# SCH_Esp12_Power_Module_2022-09-06.net
KiCad netlist of a schematic drawn in EasyEDA
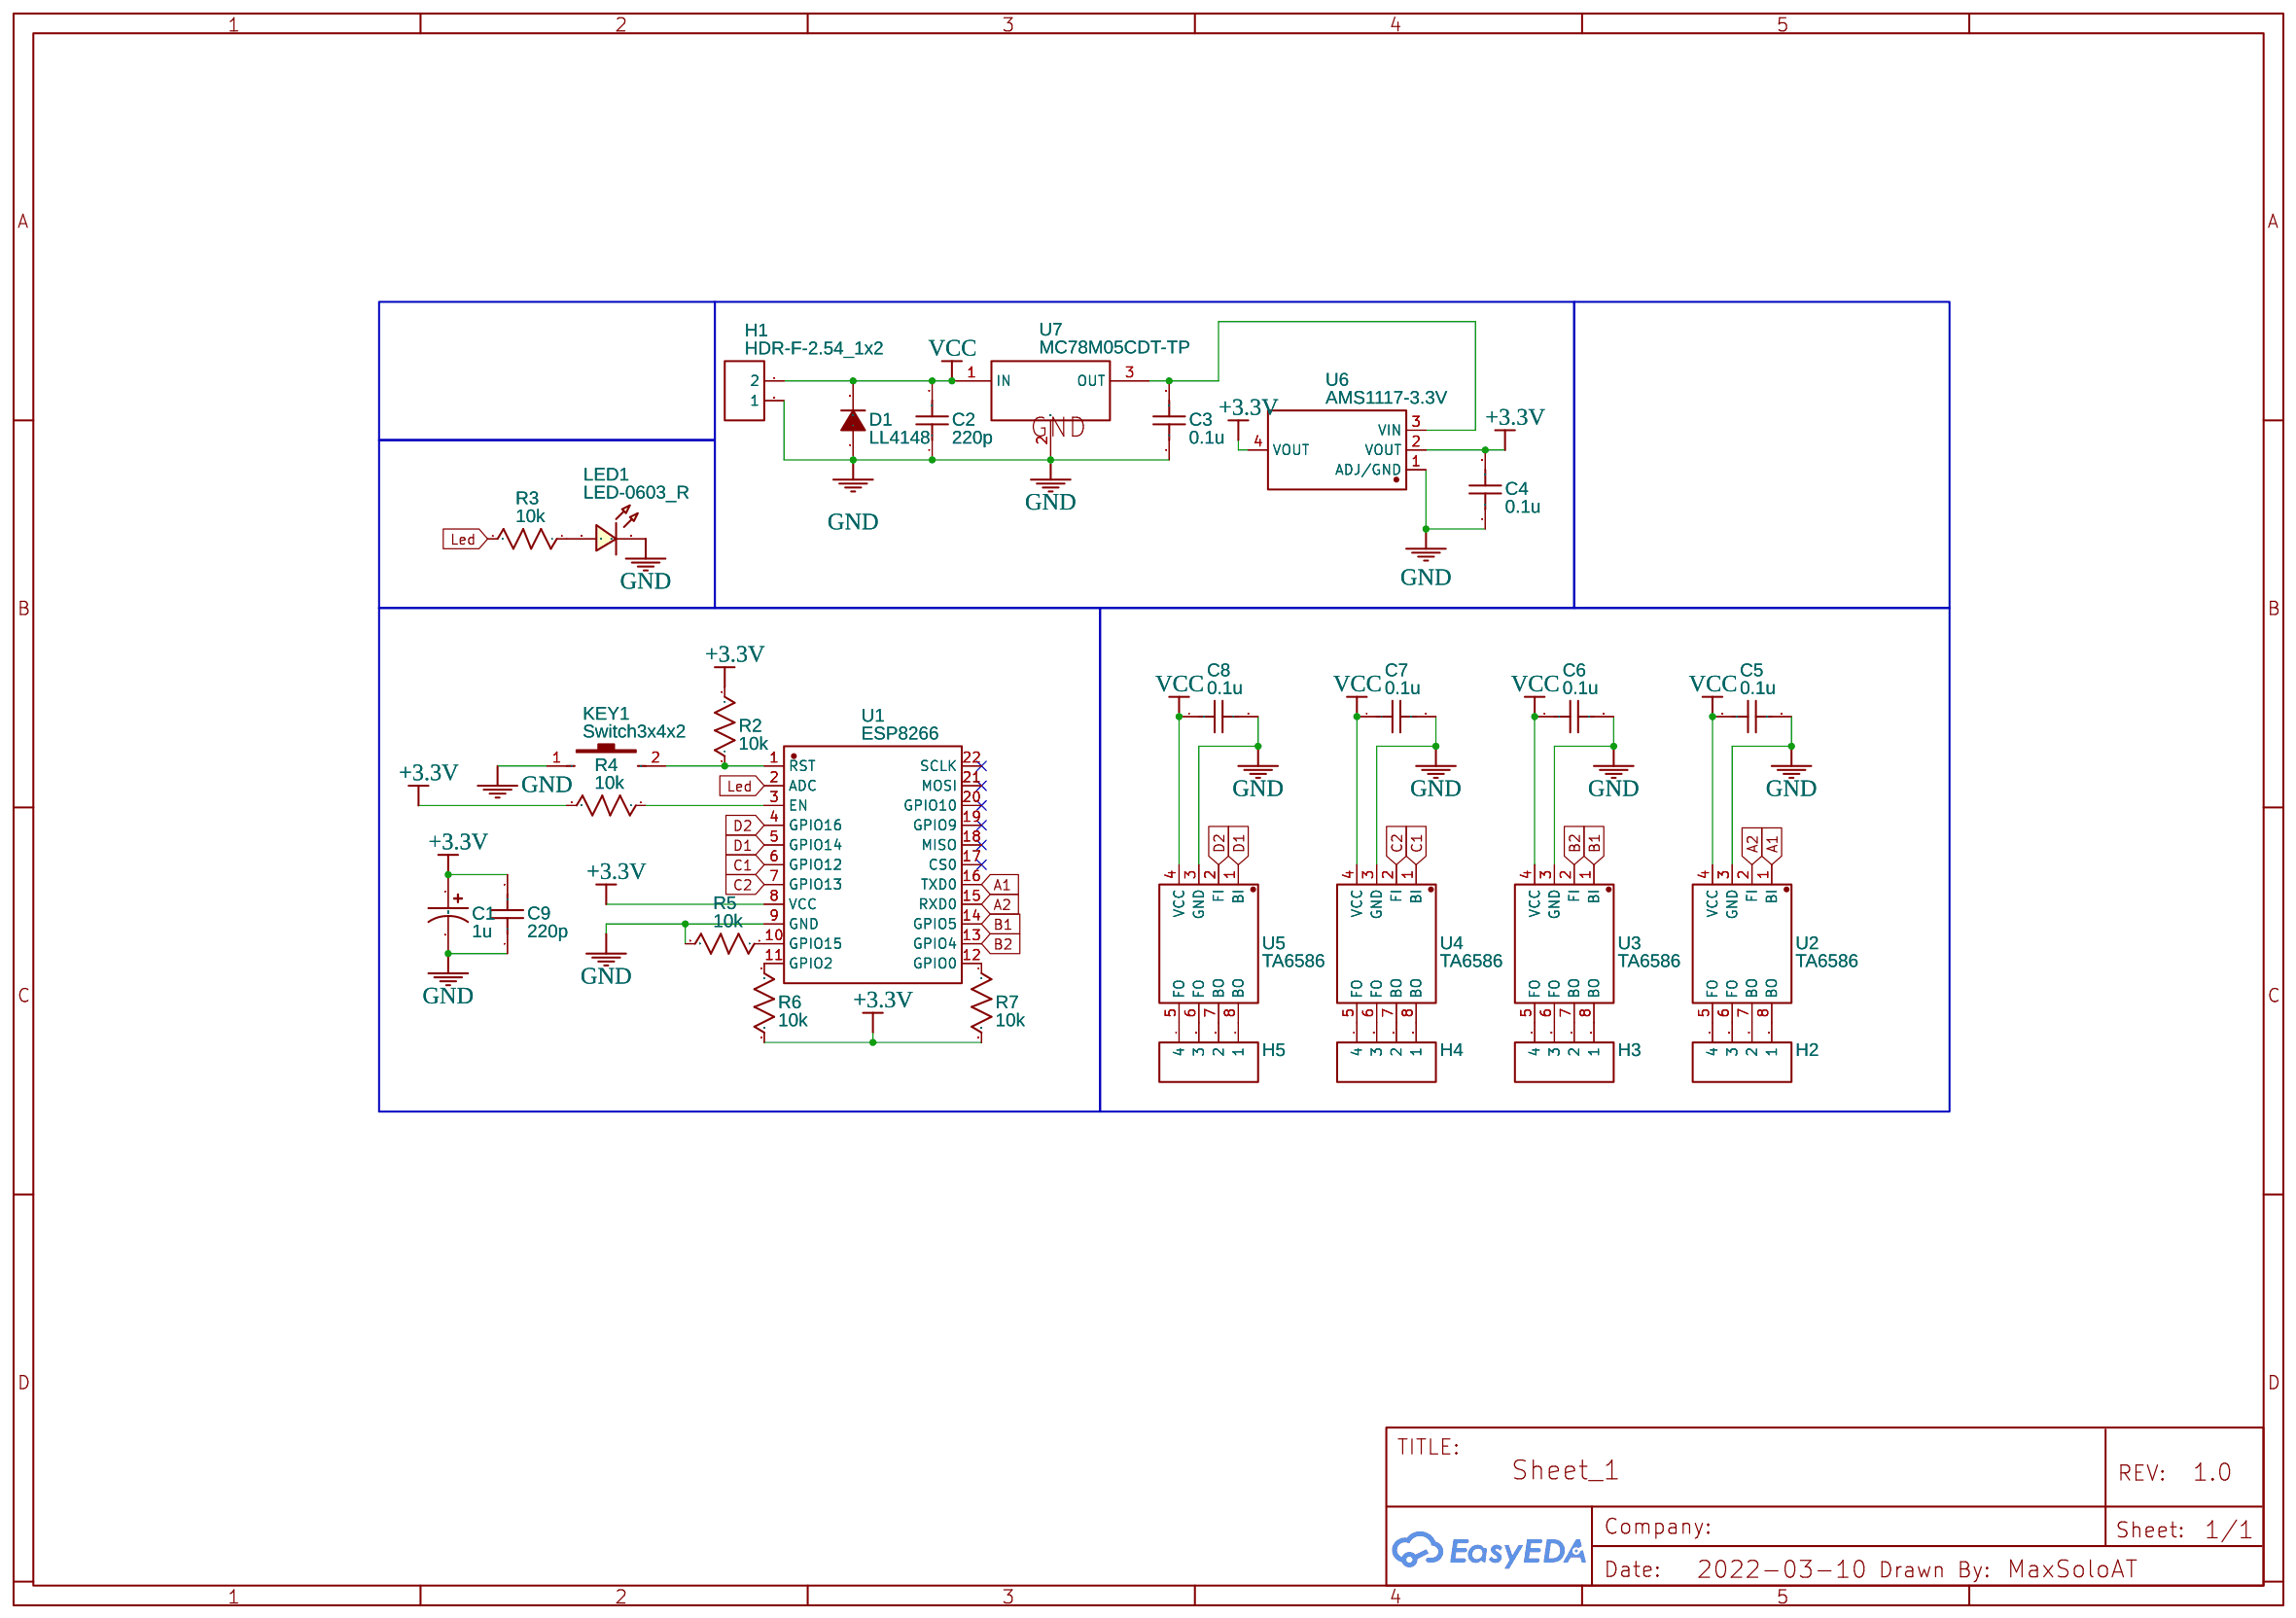
[diagram p0: schematic sheet]

(export (version "E")
  (design (tool "Eeschema 10.0.6"))
  (components
    (comp (ref "C1") (value "1u") (libsource (lib "") (part "C_Tan_SMD_B_US")))
    (comp (ref "C2") (value "220p") (libsource (lib "") (part "C_0603_US")))
    (comp (ref "C3") (value "0.1u") (libsource (lib "") (part "C_0603_US")))
    (comp (ref "C4") (value "0.1u") (libsource (lib "") (part "C_0603_US")))
    (comp (ref "C5") (value "0.1u") (libsource (lib "") (part "C_0603_US_1")))
    (comp (ref "C6") (value "0.1u") (libsource (lib "") (part "C_0603_US_1")))
    (comp (ref "C7") (value "0.1u") (libsource (lib "") (part "C_0603_US_1")))
    (comp (ref "C8") (value "0.1u") (libsource (lib "") (part "C_0603_US_1")))
    (comp (ref "C9") (value "220p") (libsource (lib "") (part "C_0603_US")))
    (comp (ref "D1")
      (value "LL4148")
      (fields (field (name "BOM_Supplier Part") "C9808"))
      (libsource (lib "") (part "LL4148"))
    )
    (comp (ref "H1")
      (value "HDR-F-2.54_1x2")
      (fields (field (name "BOM_Supplier Part") "C49661"))
      (libsource (lib "") (part "HDR-F-2.54_1x2"))
    )
    (comp (ref "H2")
      (value "HDR-F-2.54_1x4")
      (fields (field (name "BOM_Supplier Part") "C225501"))
      (libsource (lib "") (part "HDR-F-2.54_1x4"))
    )
    (comp (ref "H3")
      (value "HDR-F-2.54_1x4")
      (fields (field (name "BOM_Supplier Part") "C225501"))
      (libsource (lib "") (part "HDR-F-2.54_1x4"))
    )
    (comp (ref "H4")
      (value "HDR-F-2.54_1x4")
      (fields (field (name "BOM_Supplier Part") "C225501"))
      (libsource (lib "") (part "HDR-F-2.54_1x4"))
    )
    (comp (ref "H5")
      (value "HDR-F-2.54_1x4")
      (fields (field (name "BOM_Supplier Part") "C225501"))
      (libsource (lib "") (part "HDR-F-2.54_1x4"))
    )
    (comp (ref "KEY1")
      (value "Switch3x4x2")
      (fields (field (name "BOM_Supplier Part") "C26638"))
      (libsource (lib "") (part "Switch3x4x2"))
    )
    (comp (ref "LED1")
      (value "LED-0603_R")
      (fields
        (field (name "BOM_Manufacturer Part") "19-217/R6C-AL1M2VY/3T")
        (field (name "BOM_Supplier Part") "C72044")
      )
      (libsource (lib "") (part "LED-0603_R"))
    )
    (comp (ref "R2") (value "10k") (libsource (lib "") (part "R_0603_US_2")))
    (comp (ref "R3") (value "10k") (libsource (lib "") (part "R_0603_US_1")))
    (comp (ref "R4") (value "10k") (libsource (lib "") (part "R_0603_US_1")))
    (comp (ref "R5") (value "10k") (libsource (lib "") (part "R_0603_US_1")))
    (comp (ref "R6") (value "10k") (libsource (lib "") (part "R_0603_US")))
    (comp (ref "R7") (value "10k") (libsource (lib "") (part "R_0603_US")))
    (comp (ref "U1")
      (value "ESP8266")
      (fields (field (name "BOM_Supplier Part") "C9900003049"))
      (libsource (lib "") (part "ESP8266"))
    )
    (comp (ref "U2")
      (value "TA6586")
      (fields (field (name "BOM_Supplier Part") "C128851"))
      (libsource (lib "") (part "TA6586"))
    )
    (comp (ref "U3")
      (value "TA6586")
      (fields (field (name "BOM_Supplier Part") "C128851"))
      (libsource (lib "") (part "TA6586"))
    )
    (comp (ref "U4")
      (value "TA6586")
      (fields (field (name "BOM_Supplier Part") "C128851"))
      (libsource (lib "") (part "TA6586"))
    )
    (comp (ref "U5")
      (value "TA6586")
      (fields (field (name "BOM_Supplier Part") "C128851"))
      (libsource (lib "") (part "TA6586"))
    )
    (comp (ref "U6")
      (value "AMS1117-3.3V")
      (fields (field (name "BOM_Supplier Part") "C2688239"))
      (libsource (lib "") (part "AMS1117-3.3V"))
    )
    (comp (ref "U7")
      (value "MC78M05CDT-TP")
      (fields (field (name "BOM_Supplier Part") "C194250"))
      (libsource (lib "") (part "MC78M05CDT-TP"))
    )
  )
  (nets
    (net (code "1") (name "+3.3V") (class "Default")
      (node (ref "C1") (pin "1") (pinfunction "1_1") (pintype "unspecified"))
      (node (ref "C4") (pin "2") (pinfunction "2_2") (pintype "unspecified"))
      (node (ref "C9") (pin "2") (pinfunction "2_2") (pintype "unspecified"))
      (node (ref "R2") (pin "2") (pinfunction "2_2") (pintype "unspecified"))
      (node (ref "R4") (pin "2") (pinfunction "2_2") (pintype "unspecified"))
      (node (ref "R6") (pin "2") (pinfunction "2_2") (pintype "unspecified"))
      (node (ref "R7") (pin "2") (pinfunction "2_2") (pintype "unspecified"))
      (node (ref "U1") (pin "8") (pinfunction "VCC_8") (pintype "unspecified"))
      (node (ref "U6") (pin "2") (pinfunction "VOUT_2") (pintype "unspecified"))
      (node (ref "U6") (pin "4") (pinfunction "VOUT_4") (pintype "unspecified"))
    )
    (net (code "2") (name "A1") (class "Default")
      (node (ref "U1") (pin "16") (pinfunction "TXD0_16") (pintype "unspecified"))
      (node (ref "U2") (pin "1") (pinfunction "BI_1") (pintype "unspecified"))
    )
    (net (code "3") (name "A2") (class "Default")
      (node (ref "U1") (pin "15") (pinfunction "RXD0_15") (pintype "unspecified"))
      (node (ref "U2") (pin "2") (pinfunction "FI_2") (pintype "unspecified"))
    )
    (net (code "4") (name "B1") (class "Default")
      (node (ref "U1") (pin "14") (pinfunction "GPIO5_14") (pintype "unspecified"))
      (node (ref "U3") (pin "1") (pinfunction "BI_1") (pintype "unspecified"))
    )
    (net (code "5") (name "B2") (class "Default")
      (node (ref "U1") (pin "13") (pinfunction "GPIO4_13") (pintype "unspecified"))
      (node (ref "U3") (pin "2") (pinfunction "FI_2") (pintype "unspecified"))
    )
    (net (code "6") (name "C1") (class "Default")
      (node (ref "U1") (pin "6") (pinfunction "GPIO12_6") (pintype "unspecified"))
      (node (ref "U4") (pin "1") (pinfunction "BI_1") (pintype "unspecified"))
    )
    (net (code "7") (name "C2") (class "Default")
      (node (ref "U1") (pin "7") (pinfunction "GPIO13_7") (pintype "unspecified"))
      (node (ref "U4") (pin "2") (pinfunction "FI_2") (pintype "unspecified"))
    )
    (net (code "8") (name "D1") (class "Default")
      (node (ref "U1") (pin "5") (pinfunction "GPIO14_5") (pintype "unspecified"))
      (node (ref "U5") (pin "1") (pinfunction "BI_1") (pintype "unspecified"))
    )
    (net (code "9") (name "D2") (class "Default")
      (node (ref "U1") (pin "4") (pinfunction "GPIO16_4") (pintype "unspecified"))
      (node (ref "U5") (pin "2") (pinfunction "FI_2") (pintype "unspecified"))
    )
    (net (code "10") (name "GND") (class "Default")
      (node (ref "C1") (pin "2") (pinfunction "2_2") (pintype "unspecified"))
      (node (ref "C2") (pin "1") (pinfunction "1_1") (pintype "unspecified"))
      (node (ref "C3") (pin "1") (pinfunction "1_1") (pintype "unspecified"))
      (node (ref "C4") (pin "1") (pinfunction "1_1") (pintype "unspecified"))
      (node (ref "C5") (pin "2") (pinfunction "2_2") (pintype "unspecified"))
      (node (ref "C6") (pin "2") (pinfunction "2_2") (pintype "unspecified"))
      (node (ref "C7") (pin "2") (pinfunction "2_2") (pintype "unspecified"))
      (node (ref "C8") (pin "2") (pinfunction "2_2") (pintype "unspecified"))
      (node (ref "C9") (pin "1") (pinfunction "1_1") (pintype "unspecified"))
      (node (ref "D1") (pin "1") (pinfunction "A_1") (pintype "unspecified"))
      (node (ref "H1") (pin "1") (pinfunction "1_1") (pintype "input"))
      (node (ref "KEY1") (pin "1") (pinfunction "1_1") (pintype "input"))
      (node (ref "LED1") (pin "2") (pinfunction "2_2") (pintype "unspecified"))
      (node (ref "R5") (pin "2") (pinfunction "2_2") (pintype "unspecified"))
      (node (ref "U1") (pin "9") (pinfunction "GND_9") (pintype "unspecified"))
      (node (ref "U2") (pin "3") (pinfunction "GND_3") (pintype "unspecified"))
      (node (ref "U3") (pin "3") (pinfunction "GND_3") (pintype "unspecified"))
      (node (ref "U4") (pin "3") (pinfunction "GND_3") (pintype "unspecified"))
      (node (ref "U5") (pin "3") (pinfunction "GND_3") (pintype "unspecified"))
      (node (ref "U6") (pin "1") (pinfunction "ADJ/GND_1") (pintype "unspecified"))
      (node (ref "U7") (pin "2") (pinfunction "GND_2") (pintype "passive"))
    )
    (net (code "11") (name "Led") (class "Default")
      (node (ref "R3") (pin "2") (pinfunction "2_2") (pintype "unspecified"))
      (node (ref "U1") (pin "2") (pinfunction "ADC_2") (pintype "unspecified"))
    )
    (net (code "12") (name "Net-(H2-Pad1)") (class "Default")
      (node (ref "H2") (pin "1") (pinfunction "1_1") (pintype "unspecified"))
      (node (ref "U2") (pin "8") (pinfunction "BO_8") (pintype "unspecified"))
    )
    (net (code "13") (name "Net-(H2-Pad2)") (class "Default")
      (node (ref "H2") (pin "2") (pinfunction "2_2") (pintype "unspecified"))
      (node (ref "U2") (pin "7") (pinfunction "BO_7") (pintype "unspecified"))
    )
    (net (code "14") (name "Net-(H2-Pad3)") (class "Default")
      (node (ref "H2") (pin "3") (pinfunction "3_3") (pintype "unspecified"))
      (node (ref "U2") (pin "6") (pinfunction "FO_6") (pintype "unspecified"))
    )
    (net (code "15") (name "Net-(H2-Pad4)") (class "Default")
      (node (ref "H2") (pin "4") (pinfunction "4_4") (pintype "unspecified"))
      (node (ref "U2") (pin "5") (pinfunction "FO_5") (pintype "unspecified"))
    )
    (net (code "16") (name "Net-(H3-Pad1)") (class "Default")
      (node (ref "H3") (pin "1") (pinfunction "1_1") (pintype "unspecified"))
      (node (ref "U3") (pin "8") (pinfunction "BO_8") (pintype "unspecified"))
    )
    (net (code "17") (name "Net-(H3-Pad2)") (class "Default")
      (node (ref "H3") (pin "2") (pinfunction "2_2") (pintype "unspecified"))
      (node (ref "U3") (pin "7") (pinfunction "BO_7") (pintype "unspecified"))
    )
    (net (code "18") (name "Net-(H3-Pad3)") (class "Default")
      (node (ref "H3") (pin "3") (pinfunction "3_3") (pintype "unspecified"))
      (node (ref "U3") (pin "6") (pinfunction "FO_6") (pintype "unspecified"))
    )
    (net (code "19") (name "Net-(H3-Pad4)") (class "Default")
      (node (ref "H3") (pin "4") (pinfunction "4_4") (pintype "unspecified"))
      (node (ref "U3") (pin "5") (pinfunction "FO_5") (pintype "unspecified"))
    )
    (net (code "20") (name "Net-(H4-Pad1)") (class "Default")
      (node (ref "H4") (pin "1") (pinfunction "1_1") (pintype "unspecified"))
      (node (ref "U4") (pin "8") (pinfunction "BO_8") (pintype "unspecified"))
    )
    (net (code "21") (name "Net-(H4-Pad2)") (class "Default")
      (node (ref "H4") (pin "2") (pinfunction "2_2") (pintype "unspecified"))
      (node (ref "U4") (pin "7") (pinfunction "BO_7") (pintype "unspecified"))
    )
    (net (code "22") (name "Net-(H4-Pad3)") (class "Default")
      (node (ref "H4") (pin "3") (pinfunction "3_3") (pintype "unspecified"))
      (node (ref "U4") (pin "6") (pinfunction "FO_6") (pintype "unspecified"))
    )
    (net (code "23") (name "Net-(H4-Pad4)") (class "Default")
      (node (ref "H4") (pin "4") (pinfunction "4_4") (pintype "unspecified"))
      (node (ref "U4") (pin "5") (pinfunction "FO_5") (pintype "unspecified"))
    )
    (net (code "24") (name "Net-(H5-Pad1)") (class "Default")
      (node (ref "H5") (pin "1") (pinfunction "1_1") (pintype "unspecified"))
      (node (ref "U5") (pin "8") (pinfunction "BO_8") (pintype "unspecified"))
    )
    (net (code "25") (name "Net-(H5-Pad2)") (class "Default")
      (node (ref "H5") (pin "2") (pinfunction "2_2") (pintype "unspecified"))
      (node (ref "U5") (pin "7") (pinfunction "BO_7") (pintype "unspecified"))
    )
    (net (code "26") (name "Net-(H5-Pad3)") (class "Default")
      (node (ref "H5") (pin "3") (pinfunction "3_3") (pintype "unspecified"))
      (node (ref "U5") (pin "6") (pinfunction "FO_6") (pintype "unspecified"))
    )
    (net (code "27") (name "Net-(H5-Pad4)") (class "Default")
      (node (ref "H5") (pin "4") (pinfunction "4_4") (pintype "unspecified"))
      (node (ref "U5") (pin "5") (pinfunction "FO_5") (pintype "unspecified"))
    )
    (net (code "28") (name "Net-(LED1-Pad1)") (class "Default")
      (node (ref "LED1") (pin "1") (pinfunction "1_1") (pintype "unspecified"))
      (node (ref "R3") (pin "1") (pinfunction "1_1") (pintype "unspecified"))
    )
    (net (code "29") (name "Net-(U1-EN)") (class "Default")
      (node (ref "R4") (pin "1") (pinfunction "1_1") (pintype "unspecified"))
      (node (ref "U1") (pin "3") (pinfunction "EN_3") (pintype "unspecified"))
    )
    (net (code "30") (name "Net-(U1-GPIO0)") (class "Default")
      (node (ref "R7") (pin "1") (pinfunction "1_1") (pintype "unspecified"))
      (node (ref "U1") (pin "12") (pinfunction "GPIO0_12") (pintype "unspecified"))
    )
    (net (code "31") (name "Net-(U1-GPIO2)") (class "Default")
      (node (ref "R6") (pin "1") (pinfunction "1_1") (pintype "unspecified"))
      (node (ref "U1") (pin "11") (pinfunction "GPIO2_11") (pintype "unspecified"))
    )
    (net (code "32") (name "Net-(U1-GPIO15)") (class "Default")
      (node (ref "R5") (pin "1") (pinfunction "1_1") (pintype "unspecified"))
      (node (ref "U1") (pin "10") (pinfunction "GPIO15_10") (pintype "unspecified"))
    )
    (net (code "33") (name "Net-(U1-RST)") (class "Default")
      (node (ref "KEY1") (pin "2") (pinfunction "2_2") (pintype "input"))
      (node (ref "R2") (pin "1") (pinfunction "1_1") (pintype "unspecified"))
      (node (ref "U1") (pin "1") (pinfunction "RST_1") (pintype "unspecified"))
    )
    (net (code "34") (name "Net-(U6-VIN)") (class "Default")
      (node (ref "C3") (pin "2") (pinfunction "2_2") (pintype "unspecified"))
      (node (ref "U6") (pin "3") (pinfunction "VIN_3") (pintype "unspecified"))
      (node (ref "U7") (pin "3") (pinfunction "OUT_3") (pintype "passive"))
    )
    (net (code "35") (name "VCC") (class "Default")
      (node (ref "C2") (pin "2") (pinfunction "2_2") (pintype "unspecified"))
      (node (ref "C5") (pin "1") (pinfunction "1_1") (pintype "unspecified"))
      (node (ref "C6") (pin "1") (pinfunction "1_1") (pintype "unspecified"))
      (node (ref "C7") (pin "1") (pinfunction "1_1") (pintype "unspecified"))
      (node (ref "C8") (pin "1") (pinfunction "1_1") (pintype "unspecified"))
      (node (ref "D1") (pin "2") (pinfunction "K_2") (pintype "unspecified"))
      (node (ref "H1") (pin "2") (pinfunction "2_2") (pintype "input"))
      (node (ref "U2") (pin "4") (pinfunction "VCC_4") (pintype "unspecified"))
      (node (ref "U3") (pin "4") (pinfunction "VCC_4") (pintype "unspecified"))
      (node (ref "U4") (pin "4") (pinfunction "VCC_4") (pintype "unspecified"))
      (node (ref "U5") (pin "4") (pinfunction "VCC_4") (pintype "unspecified"))
      (node (ref "U7") (pin "1") (pinfunction "IN_1") (pintype "passive"))
    )
    (net (code "36") (name "unconnected-(U1-CS0-Pad17)") (class "Default")
      (node (ref "U1") (pin "17") (pinfunction "CS0_17") (pintype "unspecified+no_connect"))
    )
    (net (code "37") (name "unconnected-(U1-GPIO9-Pad19)") (class "Default")
      (node (ref "U1") (pin "19") (pinfunction "GPIO9_19") (pintype "unspecified+no_connect"))
    )
    (net (code "38") (name "unconnected-(U1-GPIO10-Pad20)") (class "Default")
      (node (ref "U1") (pin "20") (pinfunction "GPIO10_20") (pintype "unspecified+no_connect"))
    )
    (net (code "39") (name "unconnected-(U1-MISO-Pad18)") (class "Default")
      (node (ref "U1") (pin "18") (pinfunction "MISO_18") (pintype "unspecified+no_connect"))
    )
    (net (code "40") (name "unconnected-(U1-MOSI-Pad21)") (class "Default")
      (node (ref "U1") (pin "21") (pinfunction "MOSI_21") (pintype "unspecified+no_connect"))
    )
    (net (code "41") (name "unconnected-(U1-SCLK-Pad22)") (class "Default")
      (node (ref "U1") (pin "22") (pinfunction "SCLK_22") (pintype "unspecified+no_connect"))
    )
  )
)
